# power_distributer.net
KiCad netlist of a schematic drawn in EasyEDA
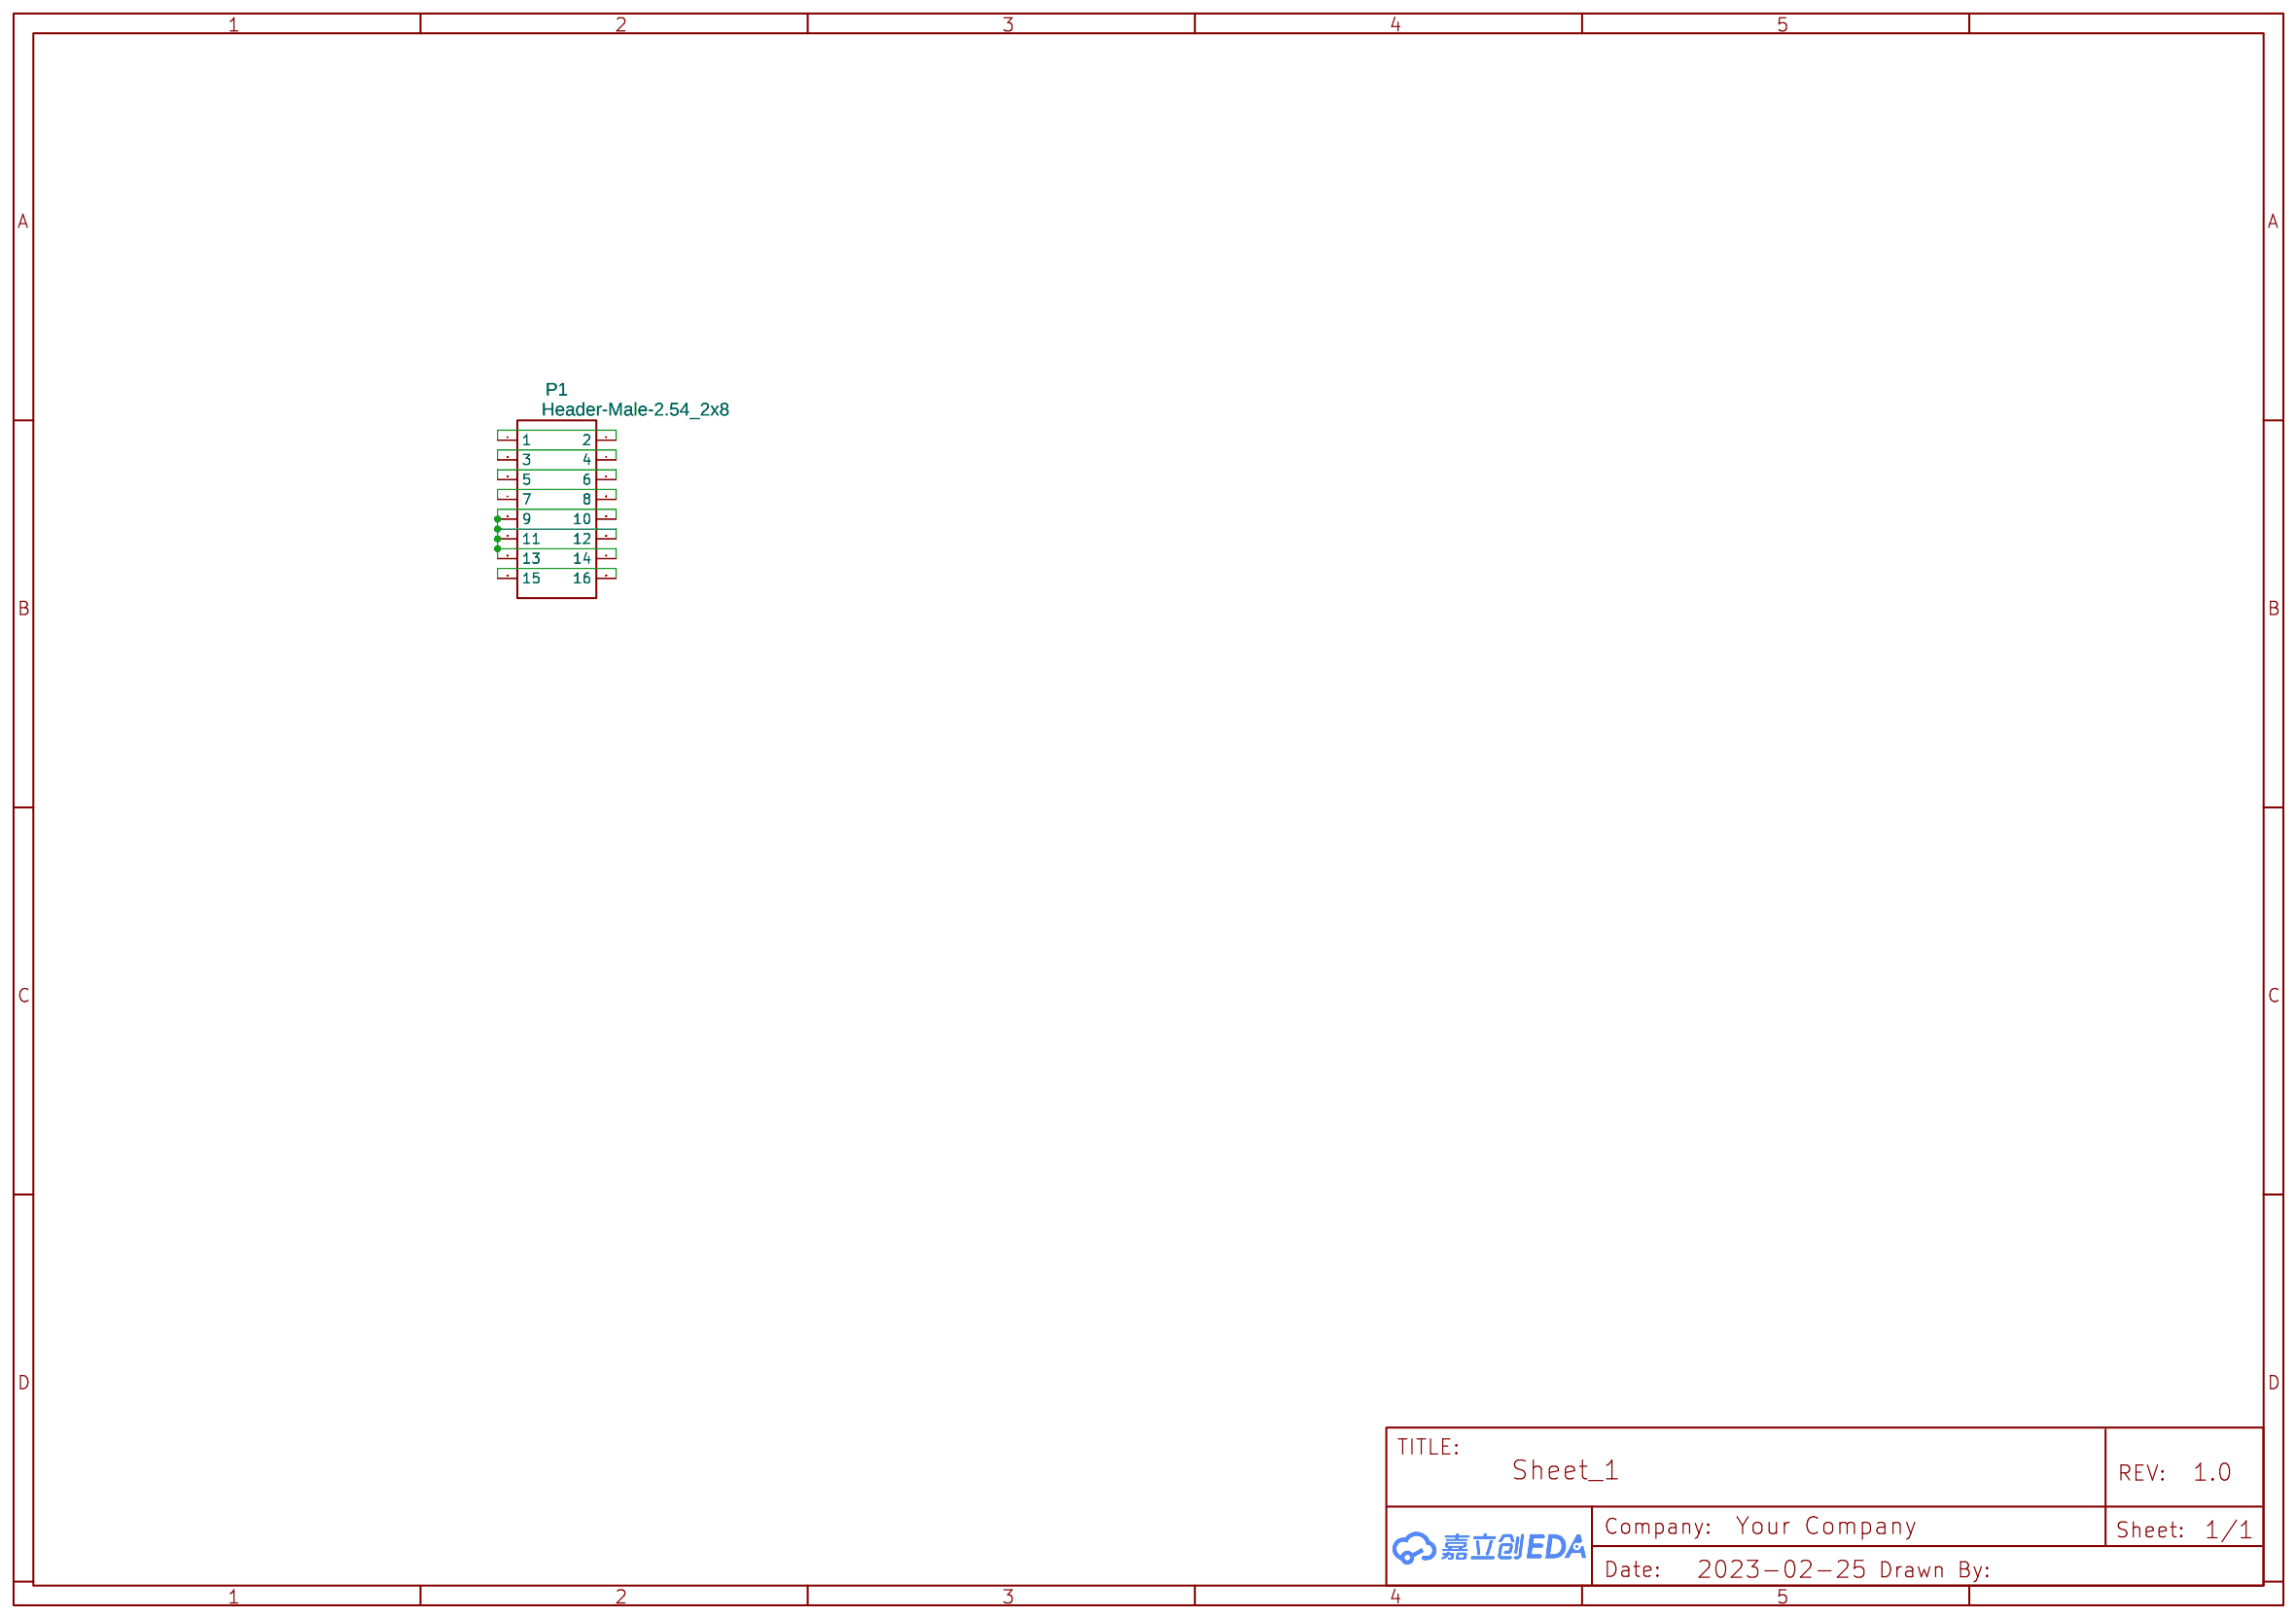
[diagram p0: schematic sheet]

(export (version "E")
  (design (tool "Eeschema 10.0.6"))
  (components
    (comp (ref "P1")
      (value "Header-Male-2.54_2x8")
      (fields (field (name "BOM_Manufacturer Part") "2.54-2*8P针") (field (name "BOM_Supplier Part") "C68234"))
      (libsource (lib "") (part "Header-Male-2.54_2x8"))
    )
  )
  (nets
    (net (code "1") (name "Net-(P1-Pad1)") (class "Default")
      (node (ref "P1") (pin "1") (pinfunction "1_1") (pintype "input"))
      (node (ref "P1") (pin "2") (pinfunction "2_2") (pintype "input"))
    )
    (net (code "2") (name "Net-(P1-Pad3)") (class "Default")
      (node (ref "P1") (pin "3") (pinfunction "3_3") (pintype "input"))
      (node (ref "P1") (pin "4") (pinfunction "4_4") (pintype "input"))
    )
    (net (code "3") (name "Net-(P1-Pad5)") (class "Default")
      (node (ref "P1") (pin "5") (pinfunction "5_5") (pintype "input"))
      (node (ref "P1") (pin "6") (pinfunction "6_6") (pintype "input"))
    )
    (net (code "4") (name "Net-(P1-Pad7)") (class "Default")
      (node (ref "P1") (pin "7") (pinfunction "7_7") (pintype "input"))
      (node (ref "P1") (pin "8") (pinfunction "8_8") (pintype "input"))
    )
    (net (code "5") (name "Net-(P1-Pad10)") (class "Default")
      (node (ref "P1") (pin "10") (pinfunction "10_10") (pintype "input"))
      (node (ref "P1") (pin "11") (pinfunction "11_11") (pintype "input"))
      (node (ref "P1") (pin "12") (pinfunction "12_12") (pintype "input"))
      (node (ref "P1") (pin "13") (pinfunction "13_13") (pintype "input"))
      (node (ref "P1") (pin "14") (pinfunction "14_14") (pintype "input"))
      (node (ref "P1") (pin "9") (pinfunction "9_9") (pintype "input"))
    )
    (net (code "6") (name "Net-(P1-Pad15)") (class "Default")
      (node (ref "P1") (pin "15") (pinfunction "15_15") (pintype "input"))
      (node (ref "P1") (pin "16") (pinfunction "16_16") (pintype "input"))
    )
  )
)
